# Arduino.net
KiCad netlist of a schematic drawn in Altium Designer
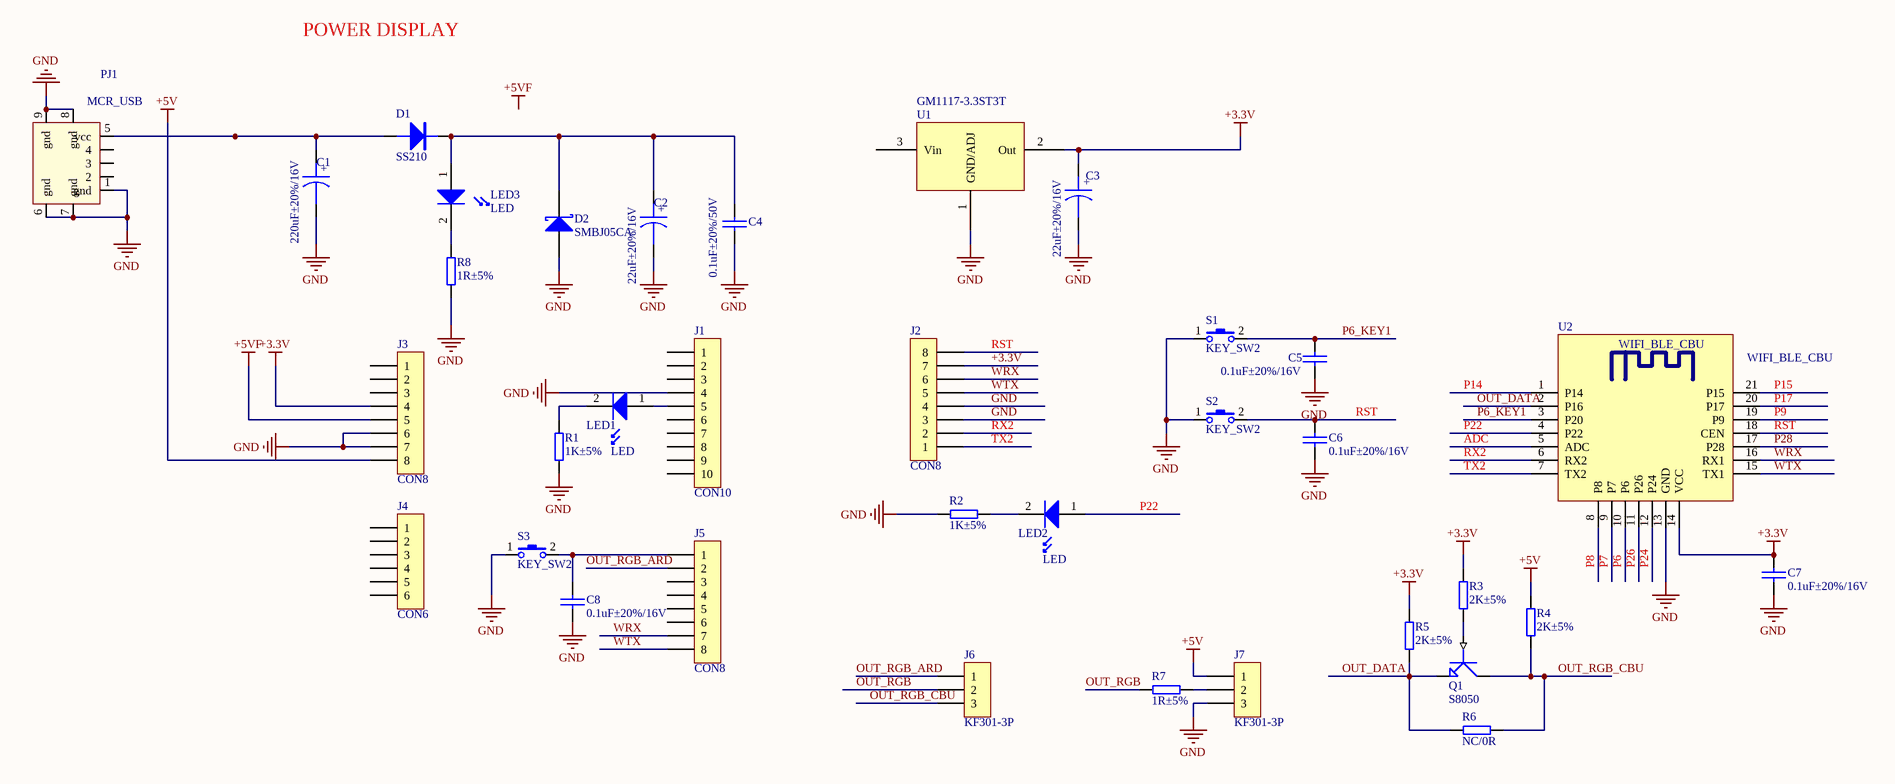
[diagram p0: Arduino幻彩灯带.SchDoc]

(export (version "E")
  (design (tool "Eeschema 10.0.6"))
  (components
    (comp (ref "C1")
      (value "220uF±20%/16V")
      (footprint "CD0.15")
      (description "Capacitor")
      (libsource (lib "*") (part "CAPACITOR POL"))
    )
    (comp (ref "C2")
      (value "22uF±20%/16V")
      (footprint "钽电容B3528")
      (description "Capacitor")
      (libsource (lib "*") (part "CAPACITOR POL"))
    )
    (comp (ref "C3")
      (value "22uF±20%/16V")
      (footprint "钽电容B3528")
      (description "Capacitor")
      (libsource (lib "*") (part "CAPACITOR POL"))
    )
    (comp (ref "C4")
      (value "0.1uF±20%/50V")
      (footprint "C0603")
      (description "Capacitor")
      (libsource (lib "昊华元件库sch") (part "CAP"))
    )
    (comp (ref "C5")
      (value "0.1uF±20%/16V")
      (footprint "C0603")
      (description "Capacitor")
      (libsource (lib "昊华元件库sch") (part "CAP"))
    )
    (comp (ref "C6")
      (value "0.1uF±20%/16V")
      (footprint "C0603")
      (description "Capacitor")
      (libsource (lib "昊华元件库sch") (part "CAP"))
    )
    (comp (ref "C7")
      (value "0.1uF±20%/16V")
      (footprint "C0603")
      (description "Capacitor")
      (libsource (lib "昊华元件库sch") (part "CAP"))
    )
    (comp (ref "C8")
      (value "0.1uF±20%/16V")
      (footprint "C0603")
      (description "Capacitor")
      (libsource (lib "昊华元件库sch") (part "CAP"))
    )
    (comp (ref "D1")
      (value "SS210")
      (footprint "SMA(DO-214AC)")
      (description "Diode")
      (libsource (lib "小马元件库sch") (part "Diode1"))
    )
    (comp (ref "D2")
      (value "SMBJ05CA")
      (footprint "SMB(DO-214AA)")
      (description "Schottky Diode")
      (fields (field (name "MFR") "Toshiba"))
      (libsource (lib "Miscellaneous Devices") (part "D Schottky"))
    )
    (comp (ref "J1")
      (value "CON10")
      (footprint "HDR1X10Z")
      (description "Connector")
      (libsource (lib "小马元件库sch") (part "CON10"))
    )
    (comp (ref "J2")
      (value "CON8")
      (footprint "HDR1X8Z")
      (description "Connector")
      (libsource (lib "小马元件库sch") (part "CON8"))
    )
    (comp (ref "J3")
      (value "CON8")
      (footprint "HDR1X8Z")
      (description "Connector")
      (libsource (lib "") (part "CON8_1"))
    )
    (comp (ref "J4")
      (value "CON6")
      (footprint "HDR1X6Z")
      (description "Connector")
      (libsource (lib "小马元件库sch") (part "CON6"))
    )
    (comp (ref "J5")
      (value "CON8")
      (footprint "HDR1X8Z")
      (description "Connector")
      (libsource (lib "") (part "CON8_1"))
    )
    (comp (ref "J6")
      (value "KF301-3P")
      (footprint "SIP3 - 2.54")
      (description "Connector")
      (libsource (lib "小马元件库sch") (part "CON3"))
    )
    (comp (ref "J7")
      (value "KF301-3P")
      (footprint "SIP3 - 2.54")
      (description "Connector")
      (libsource (lib "小马元件库sch") (part "CON3"))
    )
    (comp (ref "LED1")
      (value "LED")
      (footprint "LED0805_1")
      (fields (field (name "PUBLISHER") "*"))
      (libsource (lib "小马元件库sch") (part "LED"))
    )
    (comp (ref "LED2")
      (value "LED")
      (footprint "LED0805_1")
      (fields (field (name "PUBLISHER") "*"))
      (libsource (lib "小马元件库sch") (part "LED"))
    )
    (comp (ref "LED3")
      (value "LED")
      (footprint "LED0805_1")
      (fields (field (name "PUBLISHER") "*"))
      (libsource (lib "小马元件库sch") (part "LED"))
    )
    (comp (ref "PJ1")
      (value "MCR_USB")
      (footprint "MICRO_USB-NEW-16.12.12")
      (fields (field (name "PUBLISHER") "*"))
      (libsource (lib "昊华元件库sch") (part "MCR_USB"))
    )
    (comp (ref "Q1")
      (value "S8050")
      (footprint "SOT-23-NPN")
      (description "NPN Transistor")
      (libsource (lib "小马元件库sch") (part "NPN"))
    )
    (comp (ref "R1") (value "1K±5%") (footprint "R0603") (libsource (lib "昊华元件库sch") (part "RES5")))
    (comp (ref "R2") (value "1K±5%") (footprint "R0603") (libsource (lib "昊华元件库sch") (part "RES5")))
    (comp (ref "R3") (value "2K±5%") (footprint "R0603") (libsource (lib "昊华元件库sch") (part "RES5")))
    (comp (ref "R4") (value "2K±5%") (footprint "R0603") (libsource (lib "昊华元件库sch") (part "RES5")))
    (comp (ref "R5") (value "2K±5%") (footprint "R0603") (libsource (lib "昊华元件库sch") (part "RES5")))
    (comp (ref "R6") (value "NC/0R") (footprint "R0603") (libsource (lib "昊华元件库sch") (part "RES5")))
    (comp (ref "R7") (value "1R±5%") (footprint "R0603") (libsource (lib "昊华元件库sch") (part "RES5")))
    (comp (ref "R8") (value "1R±5%") (footprint "R0603") (libsource (lib "昊华元件库sch") (part "RES5")))
    (comp (ref "S1") (value "KEY_SW2") (footprint "KEY4-SMD") (libsource (lib "小马元件库sch") (part "KEY_SW2")))
    (comp (ref "S2") (value "KEY_SW2") (footprint "KEY4-SMD") (libsource (lib "小马元件库sch") (part "KEY_SW2")))
    (comp (ref "S3") (value "KEY_SW2") (footprint "KEY4-SMD") (libsource (lib "小马元件库sch") (part "KEY_SW2")))
    (comp (ref "U1") (value "GM1117-3.3ST3T") (footprint "SOT-223") (libsource (lib "mylib") (part "GM1117")))
    (comp (ref "U2")
      (value "WIFI_BLE_CBU")
      (footprint "WIFI_BLE_CBU")
      (description "Module")
      (libsource (lib "TYModeSchlib V03") (part "WIFI_BLE_CBU"))
    )
  )
  (nets
    (net (code "1") (name "+3.3V") (class "Default")
      (node (ref "C3") (pin "1") (pinfunction "1_1") (pintype "passive"))
      (node (ref "C7") (pin "2") (pinfunction "2_2") (pintype "passive"))
      (node (ref "J2") (pin "7") (pinfunction "7_7") (pintype "passive"))
      (node (ref "J3") (pin "4") (pinfunction "4_4") (pintype "passive"))
      (node (ref "R3") (pin "1") (pinfunction "1_1") (pintype "passive"))
      (node (ref "R5") (pin "1") (pinfunction "1_1") (pintype "passive"))
      (node (ref "U1") (pin "2") (pinfunction "Out_2") (pintype "passive"))
      (node (ref "U2") (pin "14") (pinfunction "VCC_14") (pintype "passive"))
    )
    (net (code "2") (name "+5V") (class "Default")
      (node (ref "J3") (pin "8") (pinfunction "8_8") (pintype "passive"))
      (node (ref "J7") (pin "1") (pinfunction "1_1") (pintype "passive"))
      (node (ref "R4") (pin "1") (pinfunction "1_1") (pintype "passive"))
    )
    (net (code "3") (name "+5VF") (class "Default")
      (node (ref "J3") (pin "5") (pinfunction "5_5") (pintype "passive"))
    )
    (net (code "4") (name "/ADC") (class "Default")
      (node (ref "U2") (pin "5") (pinfunction "ADC_5") (pintype "passive"))
    )
    (net (code "5") (name "/OUT_DATA") (class "Default")
      (node (ref "Q1") (pin "1") (pinfunction "E_1") (pintype "passive"))
      (node (ref "R5") (pin "2") (pinfunction "2_2") (pintype "passive"))
      (node (ref "R6") (pin "1") (pinfunction "1_1") (pintype "passive"))
      (node (ref "U2") (pin "2") (pinfunction "P16_2") (pintype "passive"))
    )
    (net (code "6") (name "/OUT_RGB") (class "Default")
      (node (ref "J6") (pin "2") (pinfunction "2_2") (pintype "passive"))
      (node (ref "R7") (pin "1") (pinfunction "1_1") (pintype "passive"))
    )
    (net (code "7") (name "/OUT_RGB_ARD") (class "Default")
      (node (ref "J5") (pin "2") (pinfunction "2_2") (pintype "passive"))
      (node (ref "J6") (pin "1") (pinfunction "1_1") (pintype "passive"))
    )
    (net (code "8") (name "/OUT_RGB_CBU") (class "Default")
      (node (ref "J6") (pin "3") (pinfunction "3_3") (pintype "passive"))
      (node (ref "Q1") (pin "3") (pinfunction "C_3") (pintype "passive"))
      (node (ref "R4") (pin "2") (pinfunction "2_2") (pintype "passive"))
      (node (ref "R6") (pin "2") (pinfunction "2_2") (pintype "passive"))
    )
    (net (code "9") (name "/P6") (class "Default")
      (node (ref "U2") (pin "10") (pinfunction "P6_10") (pintype "passive"))
    )
    (net (code "10") (name "/P6_KEY1") (class "Default")
      (node (ref "C5") (pin "2") (pinfunction "2_2") (pintype "passive"))
      (node (ref "S1") (pin "2") (pinfunction "2_2") (pintype "passive"))
      (node (ref "U2") (pin "3") (pinfunction "P20_3") (pintype "passive"))
    )
    (net (code "11") (name "/P7") (class "Default")
      (node (ref "U2") (pin "9") (pinfunction "P7_9") (pintype "passive"))
    )
    (net (code "12") (name "/P8") (class "Default")
      (node (ref "U2") (pin "8") (pinfunction "P8_8") (pintype "passive"))
    )
    (net (code "13") (name "/P9") (class "Default")
      (node (ref "U2") (pin "19") (pinfunction "P9_19") (pintype "passive"))
    )
    (net (code "14") (name "/P14") (class "Default")
      (node (ref "U2") (pin "1") (pinfunction "P14_1") (pintype "passive"))
    )
    (net (code "15") (name "/P15") (class "Default")
      (node (ref "U2") (pin "21") (pinfunction "P15_21") (pintype "passive"))
    )
    (net (code "16") (name "/P17") (class "Default")
      (node (ref "U2") (pin "20") (pinfunction "P17_20") (pintype "passive"))
    )
    (net (code "17") (name "/P22") (class "Default")
      (node (ref "LED2") (pin "1") (pinfunction "1_1") (pintype "passive"))
      (node (ref "U2") (pin "4") (pinfunction "P22_4") (pintype "passive"))
    )
    (net (code "18") (name "/P24") (class "Default")
      (node (ref "U2") (pin "12") (pinfunction "P24_12") (pintype "passive"))
    )
    (net (code "19") (name "/P26") (class "Default")
      (node (ref "U2") (pin "11") (pinfunction "P26_11") (pintype "passive"))
    )
    (net (code "20") (name "/P28") (class "Default")
      (node (ref "U2") (pin "17") (pinfunction "P28_17") (pintype "passive"))
    )
    (net (code "21") (name "/RST") (class "Default")
      (node (ref "C6") (pin "1") (pinfunction "1_1") (pintype "passive"))
      (node (ref "J2") (pin "8") (pinfunction "8_8") (pintype "passive"))
      (node (ref "S2") (pin "2") (pinfunction "2_2") (pintype "passive"))
      (node (ref "U2") (pin "18") (pinfunction "CEN_18") (pintype "passive"))
    )
    (net (code "22") (name "/RX2") (class "Default")
      (node (ref "J2") (pin "2") (pinfunction "2_2") (pintype "passive"))
      (node (ref "U2") (pin "6") (pinfunction "RX2_6") (pintype "passive"))
    )
    (net (code "23") (name "/TX2") (class "Default")
      (node (ref "J2") (pin "1") (pinfunction "1_1") (pintype "passive"))
      (node (ref "U2") (pin "7") (pinfunction "TX2_7") (pintype "passive"))
    )
    (net (code "24") (name "/WRX") (class "Default")
      (node (ref "J2") (pin "6") (pinfunction "6_6") (pintype "passive"))
      (node (ref "J5") (pin "7") (pinfunction "7_7") (pintype "passive"))
      (node (ref "U2") (pin "16") (pinfunction "RX1_16") (pintype "passive"))
    )
    (net (code "25") (name "/WTX") (class "Default")
      (node (ref "J2") (pin "5") (pinfunction "5_5") (pintype "passive"))
      (node (ref "J5") (pin "8") (pinfunction "8_8") (pintype "passive"))
      (node (ref "U2") (pin "15") (pinfunction "TX1_15") (pintype "passive"))
    )
    (net (code "26") (name "GND") (class "Default")
      (node (ref "C1") (pin "2") (pinfunction "2_2") (pintype "passive"))
      (node (ref "C2") (pin "2") (pinfunction "2_2") (pintype "passive"))
      (node (ref "C3") (pin "2") (pinfunction "2_2") (pintype "passive"))
      (node (ref "C4") (pin "2") (pinfunction "2_2") (pintype "passive"))
      (node (ref "C5") (pin "1") (pinfunction "1_1") (pintype "passive"))
      (node (ref "C6") (pin "2") (pinfunction "2_2") (pintype "passive"))
      (node (ref "C7") (pin "1") (pinfunction "1_1") (pintype "passive"))
      (node (ref "C8") (pin "1") (pinfunction "1_1") (pintype "passive"))
      (node (ref "D2") (pin "1") (pinfunction "A_1") (pintype "passive"))
      (node (ref "J1") (pin "4") (pinfunction "4_4") (pintype "passive"))
      (node (ref "J2") (pin "3") (pinfunction "3_3") (pintype "passive"))
      (node (ref "J2") (pin "4") (pinfunction "4_4") (pintype "passive"))
      (node (ref "J3") (pin "6") (pinfunction "6_6") (pintype "passive"))
      (node (ref "J3") (pin "7") (pinfunction "7_7") (pintype "passive"))
      (node (ref "J7") (pin "3") (pinfunction "3_3") (pintype "passive"))
      (node (ref "PJ1") (pin "1") (pinfunction "gnd_1") (pintype "passive"))
      (node (ref "PJ1") (pin "6") (pinfunction "gnd_6") (pintype "passive"))
      (node (ref "PJ1") (pin "7") (pinfunction "gnd_7") (pintype "passive"))
      (node (ref "PJ1") (pin "8") (pinfunction "gnd_8") (pintype "passive"))
      (node (ref "PJ1") (pin "9") (pinfunction "gnd_9") (pintype "passive"))
      (node (ref "R1") (pin "1") (pinfunction "1_1") (pintype "passive"))
      (node (ref "R2") (pin "2") (pinfunction "2_2") (pintype "passive"))
      (node (ref "R8") (pin "1") (pinfunction "1_1") (pintype "passive"))
      (node (ref "S1") (pin "1") (pinfunction "1_1") (pintype "passive"))
      (node (ref "S2") (pin "1") (pinfunction "1_1") (pintype "passive"))
      (node (ref "S3") (pin "1") (pinfunction "1_1") (pintype "passive"))
      (node (ref "U1") (pin "1") (pinfunction "GND/ADJ_1") (pintype "passive"))
      (node (ref "U2") (pin "13") (pinfunction "GND_13") (pintype "passive"))
    )
    (net (code "27") (name "Net-(C8-Pad2)") (class "Default")
      (node (ref "C8") (pin "2") (pinfunction "2_2") (pintype "passive"))
      (node (ref "J5") (pin "1") (pinfunction "1_1") (pintype "passive"))
      (node (ref "S3") (pin "2") (pinfunction "2_2") (pintype "passive"))
    )
    (net (code "28") (name "Net-(D2-K)") (class "Default")
      (node (ref "C2") (pin "1") (pinfunction "1_1") (pintype "passive"))
      (node (ref "C4") (pin "1") (pinfunction "1_1") (pintype "passive"))
      (node (ref "D1") (pin "2") (pinfunction "2_2") (pintype "passive"))
      (node (ref "D2") (pin "2") (pinfunction "K_2") (pintype "passive"))
      (node (ref "LED3") (pin "1") (pinfunction "1_1") (pintype "passive"))
    )
    (net (code "29") (name "Net-(J1-Pad5)") (class "Default")
      (node (ref "J1") (pin "5") (pinfunction "5_5") (pintype "passive"))
      (node (ref "LED1") (pin "1") (pinfunction "1_1") (pintype "passive"))
    )
    (net (code "30") (name "Net-(J7-Pad2)") (class "Default")
      (node (ref "J7") (pin "2") (pinfunction "2_2") (pintype "passive"))
      (node (ref "R7") (pin "2") (pinfunction "2_2") (pintype "passive"))
    )
    (net (code "31") (name "Net-(LED1-Pad2)") (class "Default")
      (node (ref "LED1") (pin "2") (pinfunction "2_2") (pintype "passive"))
      (node (ref "R1") (pin "2") (pinfunction "2_2") (pintype "passive"))
    )
    (net (code "32") (name "Net-(LED2-Pad2)") (class "Default")
      (node (ref "LED2") (pin "2") (pinfunction "2_2") (pintype "passive"))
      (node (ref "R2") (pin "1") (pinfunction "1_1") (pintype "passive"))
    )
    (net (code "33") (name "Net-(LED3-Pad2)") (class "Default")
      (node (ref "LED3") (pin "2") (pinfunction "2_2") (pintype "passive"))
      (node (ref "R8") (pin "2") (pinfunction "2_2") (pintype "passive"))
    )
    (net (code "34") (name "Net-(PJ1-vcc)") (class "Default")
      (node (ref "C1") (pin "1") (pinfunction "1_1") (pintype "passive"))
      (node (ref "D1") (pin "1") (pinfunction "1_1") (pintype "passive"))
      (node (ref "PJ1") (pin "5") (pinfunction "vcc_5") (pintype "passive"))
    )
    (net (code "35") (name "Net-(Q1-B)") (class "Default")
      (node (ref "Q1") (pin "2") (pinfunction "B_2") (pintype "input"))
      (node (ref "R3") (pin "2") (pinfunction "2_2") (pintype "passive"))
    )
    (net (code "36") (name "unconnected-(J1-Pad1)") (class "Default")
      (node (ref "J1") (pin "1") (pinfunction "1_1") (pintype "passive"))
    )
    (net (code "37") (name "unconnected-(J1-Pad2)") (class "Default")
      (node (ref "J1") (pin "2") (pinfunction "2_2") (pintype "passive"))
    )
    (net (code "38") (name "unconnected-(J1-Pad3)") (class "Default")
      (node (ref "J1") (pin "3") (pinfunction "3_3") (pintype "passive"))
    )
    (net (code "39") (name "unconnected-(J1-Pad6)") (class "Default")
      (node (ref "J1") (pin "6") (pinfunction "6_6") (pintype "passive"))
    )
    (net (code "40") (name "unconnected-(J1-Pad7)") (class "Default")
      (node (ref "J1") (pin "7") (pinfunction "7_7") (pintype "passive"))
    )
    (net (code "41") (name "unconnected-(J1-Pad8)") (class "Default")
      (node (ref "J1") (pin "8") (pinfunction "8_8") (pintype "passive"))
    )
    (net (code "42") (name "unconnected-(J1-Pad9)") (class "Default")
      (node (ref "J1") (pin "9") (pinfunction "9_9") (pintype "passive"))
    )
    (net (code "43") (name "unconnected-(J1-Pad10)") (class "Default")
      (node (ref "J1") (pin "10") (pinfunction "10_10") (pintype "passive"))
    )
    (net (code "44") (name "unconnected-(J3-Pad1)") (class "Default")
      (node (ref "J3") (pin "1") (pinfunction "1_1") (pintype "passive"))
    )
    (net (code "45") (name "unconnected-(J3-Pad2)") (class "Default")
      (node (ref "J3") (pin "2") (pinfunction "2_2") (pintype "passive"))
    )
    (net (code "46") (name "unconnected-(J3-Pad3)") (class "Default")
      (node (ref "J3") (pin "3") (pinfunction "3_3") (pintype "passive"))
    )
    (net (code "47") (name "unconnected-(J4-Pad1)") (class "Default")
      (node (ref "J4") (pin "1") (pinfunction "1_1") (pintype "passive"))
    )
    (net (code "48") (name "unconnected-(J4-Pad2)") (class "Default")
      (node (ref "J4") (pin "2") (pinfunction "2_2") (pintype "passive"))
    )
    (net (code "49") (name "unconnected-(J4-Pad3)") (class "Default")
      (node (ref "J4") (pin "3") (pinfunction "3_3") (pintype "passive"))
    )
    (net (code "50") (name "unconnected-(J4-Pad4)") (class "Default")
      (node (ref "J4") (pin "4") (pinfunction "4_4") (pintype "passive"))
    )
    (net (code "51") (name "unconnected-(J4-Pad5)") (class "Default")
      (node (ref "J4") (pin "5") (pinfunction "5_5") (pintype "passive"))
    )
    (net (code "52") (name "unconnected-(J4-Pad6)") (class "Default")
      (node (ref "J4") (pin "6") (pinfunction "6_6") (pintype "passive"))
    )
    (net (code "53") (name "unconnected-(J5-Pad3)") (class "Default")
      (node (ref "J5") (pin "3") (pinfunction "3_3") (pintype "passive"))
    )
    (net (code "54") (name "unconnected-(J5-Pad4)") (class "Default")
      (node (ref "J5") (pin "4") (pinfunction "4_4") (pintype "passive"))
    )
    (net (code "55") (name "unconnected-(J5-Pad5)") (class "Default")
      (node (ref "J5") (pin "5") (pinfunction "5_5") (pintype "passive"))
    )
    (net (code "56") (name "unconnected-(J5-Pad6)") (class "Default")
      (node (ref "J5") (pin "6") (pinfunction "6_6") (pintype "passive"))
    )
    (net (code "57") (name "unconnected-(PJ1-Pad2)") (class "Default")
      (node (ref "PJ1") (pin "2") (pinfunction "2_2") (pintype "passive"))
    )
    (net (code "58") (name "unconnected-(PJ1-Pad3)") (class "Default")
      (node (ref "PJ1") (pin "3") (pinfunction "3_3") (pintype "passive"))
    )
    (net (code "59") (name "unconnected-(PJ1-Pad4)") (class "Default")
      (node (ref "PJ1") (pin "4") (pinfunction "4_4") (pintype "passive"))
    )
    (net (code "60") (name "unconnected-(U1-Vin-Pad3)") (class "Default")
      (node (ref "U1") (pin "3") (pinfunction "Vin_3") (pintype "passive"))
    )
  )
)
